# Main.net
KiCad netlist of a schematic drawn in Altium Designer
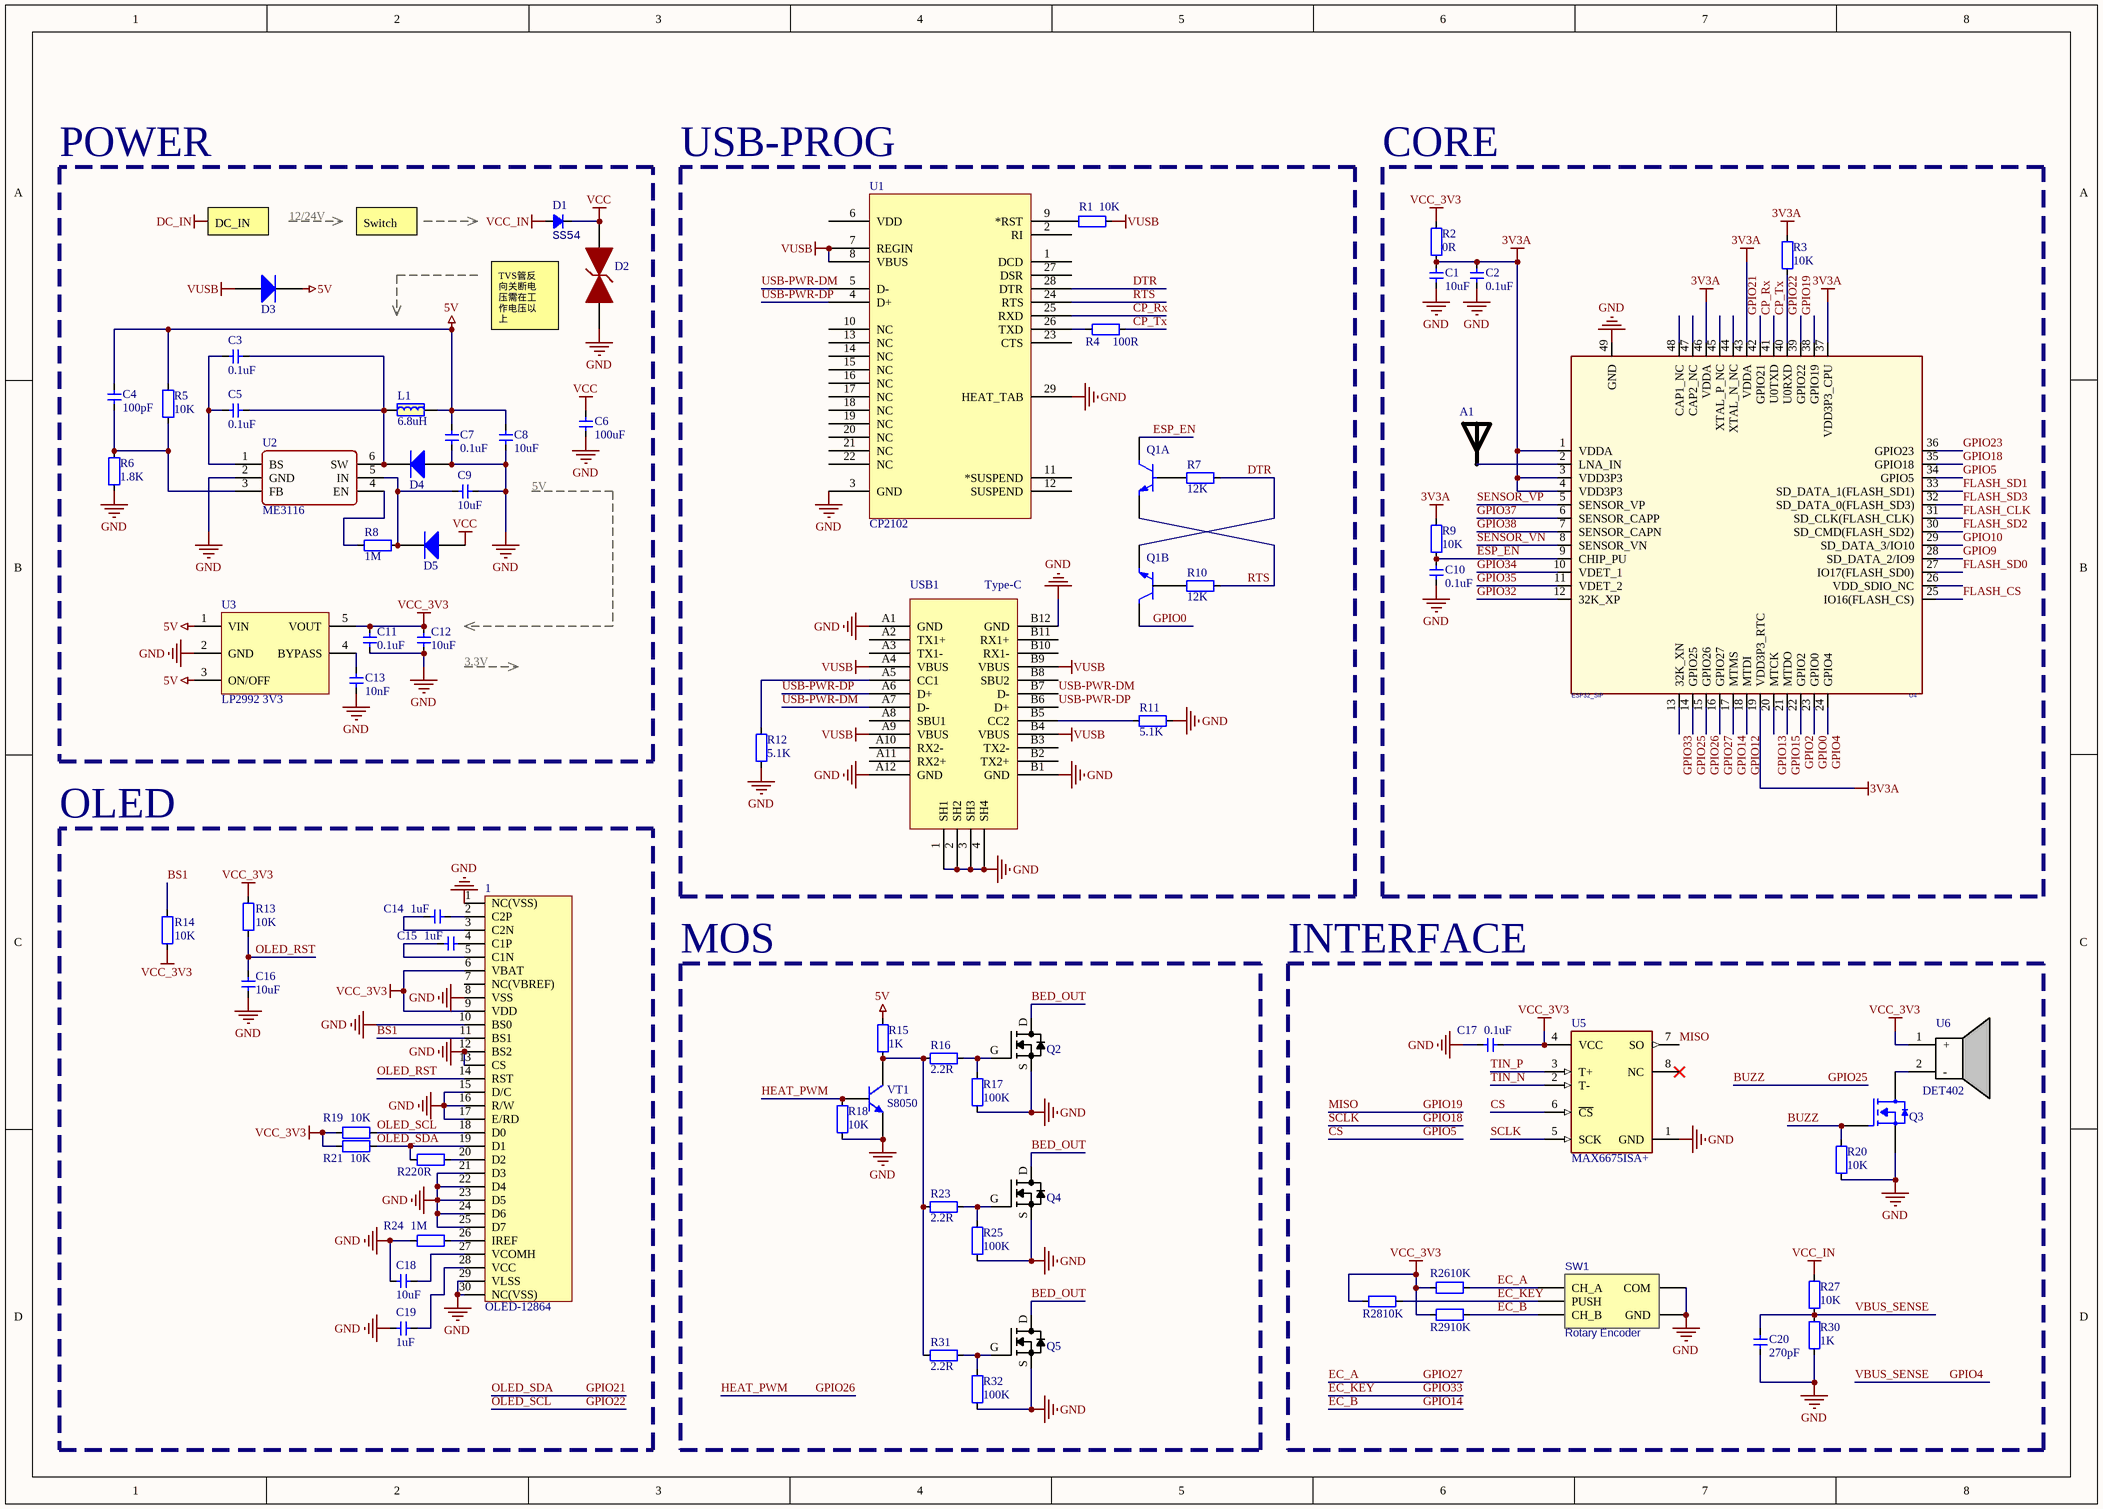
[diagram p0: Main.SchDoc]

(export (version "E")
  (design (tool "Eeschema 10.0.6"))
  (components
    (comp (ref "1")
      (value "OLED-12864")
      (footprint "OLED-12864-1.3-TOP")
      (description "显示屏")
      (libsource (lib "MyPcbLib") (part "OLED-12864"))
    )
    (comp (ref "A1")
      (value "RAINSUN")
      (footprint "ANT-Rainsun-AN5120")
      (libsource (lib "MyPcbLib") (part "ANT-Rainsun-AP5120"))
    )
    (comp (ref "C1")
      (value "10uF")
      (footprint "CAP_0402")
      (description "Capacitor")
      (libsource (lib "MyPcbLib") (part "电容-0402"))
    )
    (comp (ref "C2")
      (value "0.1uF")
      (footprint "CAP_0402")
      (description "Capacitor")
      (libsource (lib "MyPcbLib") (part "电容-0402"))
    )
    (comp (ref "C3")
      (value "0.1uF")
      (footprint "CAP_0402")
      (description "Capacitor")
      (libsource (lib "MyPcbLib") (part "电容-0402"))
    )
    (comp (ref "C4")
      (value "100pF")
      (footprint "CAP_0402")
      (description "Capacitor")
      (libsource (lib "MyPcbLib") (part "电容-0402"))
    )
    (comp (ref "C5")
      (value "0.1uF")
      (footprint "CAP_0402")
      (description "Capacitor")
      (libsource (lib "MyPcbLib") (part "电容-0402"))
    )
    (comp (ref "C6")
      (value "100uF")
      (footprint "1206-CAP")
      (description "Capacitor")
      (libsource (lib "MyPcbLib") (part "电容-1206"))
    )
    (comp (ref "C7")
      (value "0.1uF")
      (footprint "CAP_0402")
      (description "Capacitor")
      (libsource (lib "MyPcbLib") (part "电容-0402"))
    )
    (comp (ref "C8")
      (value "10uF")
      (footprint "CAP_0402")
      (description "Capacitor")
      (libsource (lib "MyPcbLib") (part "电容-0402"))
    )
    (comp (ref "C9")
      (value "10uF")
      (footprint "CAP_0402")
      (description "Capacitor")
      (libsource (lib "MyPcbLib") (part "电容-0402"))
    )
    (comp (ref "C10")
      (value "0.1uF")
      (footprint "CAP_0402")
      (description "Capacitor")
      (libsource (lib "MyPcbLib") (part "电容-0402"))
    )
    (comp (ref "C11")
      (value "0.1uF")
      (footprint "CAP_0402")
      (description "Capacitor")
      (libsource (lib "MyPcbLib") (part "电容-0402"))
    )
    (comp (ref "C12")
      (value "10uF")
      (footprint "CAP_0402")
      (description "Capacitor")
      (libsource (lib "MyPcbLib") (part "电容-0402"))
    )
    (comp (ref "C13")
      (value "10nF")
      (footprint "CAP_0402")
      (description "Capacitor")
      (libsource (lib "MyPcbLib") (part "电容-0402"))
    )
    (comp (ref "C14")
      (value "1uF")
      (footprint "CAP_0402")
      (description "Capacitor")
      (libsource (lib "MyPcbLib") (part "电容-0402"))
    )
    (comp (ref "C15")
      (value "1uF")
      (footprint "CAP_0402")
      (description "Capacitor")
      (libsource (lib "MyPcbLib") (part "电容-0402"))
    )
    (comp (ref "C16")
      (value "10uF")
      (footprint "CAP_0402")
      (description "Capacitor")
      (libsource (lib "MyPcbLib") (part "电容-0402"))
    )
    (comp (ref "C17")
      (value "0.1uF")
      (footprint "CAP_0402")
      (description "Capacitor")
      (libsource (lib "MyPcbLib") (part "电容-0402"))
    )
    (comp (ref "C18")
      (value "10uF")
      (footprint "CAP_0402")
      (description "Capacitor")
      (libsource (lib "MyPcbLib") (part "电容-0402"))
    )
    (comp (ref "C19")
      (value "1uF")
      (footprint "CAP_0402")
      (description "Capacitor")
      (libsource (lib "MyPcbLib") (part "电容-0402"))
    )
    (comp (ref "C20")
      (value "270pF")
      (footprint "CAP_0402")
      (description "Capacitor")
      (libsource (lib "MyPcbLib") (part "电容-0402"))
    )
    (comp (ref "D1")
      (value "SS54")
      (footprint "DO-214AC")
      (description "Diode")
      (libsource (lib "KitSprout") (part "Diode_SMA"))
    )
    (comp (ref "D2")
      (value "SMBJ28CA")
      (footprint "SMBJ-CA_MFG")
      (libsource (lib "MyPcbLib") (part "SMBJ28CA"))
    )
    (comp (ref "D3")
      (value "二极管-5819W")
      (footprint "SOD-323")
      (description "40V")
      (libsource (lib "MyPcbLib") (part "二极管-5819W"))
    )
    (comp (ref "D4")
      (value "二极管-5819W")
      (footprint "SOD-323")
      (description "40V")
      (libsource (lib "MyPcbLib") (part "二极管-5819W"))
    )
    (comp (ref "D5")
      (value "二极管-5819W")
      (footprint "SOD-323")
      (description "40V")
      (libsource (lib "MyPcbLib") (part "二极管-5819W"))
    )
    (comp (ref "L1") (value "6.8uH") (footprint "IND-201612") (libsource (lib "MyPcbLib") (part "电感-201612")))
    (comp (ref "Q1")
      (value "BC847BVC-7")
      (footprint "SOT563-6")
      (libsource (lib "MyPcbLib") (part "BC847BVC-7"))
    )
    (comp (ref "Q2")
      (value "NTMFS5C628NLT")
      (footprint "SO8FL")
      (description "MOSFET N-CH 60V SO8FL")
      (fields
        (field (name "MANUFACTURER") "ON Semiconductor")
        (field (name "MANUFACTURER PART NUMBER") "NTMFS5C628NLT1G")
      )
      (libsource (lib "MyPcbLib") (part "NTMFS5C628NLT"))
    )
    (comp (ref "Q3")
      (value "AO3400A")
      (footprint "SOT23-3")
      (description "N-MOS")
      (libsource (lib "MyPcbLib") (part "AO3400A"))
    )
    (comp (ref "Q4")
      (value "NTMFS5C628NLT")
      (footprint "SO8FL")
      (description "MOSFET N-CH 60V SO8FL")
      (fields
        (field (name "MANUFACTURER") "ON Semiconductor")
        (field (name "MANUFACTURER PART NUMBER") "NTMFS5C628NLT1G")
      )
      (libsource (lib "MyPcbLib") (part "NTMFS5C628NLT"))
    )
    (comp (ref "Q5")
      (value "NTMFS5C628NLT")
      (footprint "SO8FL")
      (description "MOSFET N-CH 60V SO8FL")
      (fields
        (field (name "MANUFACTURER") "ON Semiconductor")
        (field (name "MANUFACTURER PART NUMBER") "NTMFS5C628NLT1G")
      )
      (libsource (lib "MyPcbLib") (part "NTMFS5C628NLT"))
    )
    (comp (ref "R1")
      (value "10K")
      (footprint "RES_0402")
      (description "Resistor")
      (libsource (lib "MyPcbLib") (part "电阻-0402"))
    )
    (comp (ref "R2")
      (value "0R")
      (footprint "RES_0402")
      (description "Resistor")
      (libsource (lib "") (part "电阻-0402_2"))
    )
    (comp (ref "R3")
      (value "10K")
      (footprint "RES_0402")
      (description "Resistor")
      (libsource (lib "") (part "电阻-0402_1"))
    )
    (comp (ref "R4")
      (value "100R")
      (footprint "RES_0402")
      (description "Resistor")
      (libsource (lib "MyPcbLib") (part "电阻-0402"))
    )
    (comp (ref "R5")
      (value "10K")
      (footprint "RES_0402")
      (description "Resistor")
      (libsource (lib "") (part "电阻-0402_1"))
    )
    (comp (ref "R6")
      (value "1.8K")
      (footprint "RES_0402")
      (description "Resistor")
      (libsource (lib "") (part "电阻-0402_1"))
    )
    (comp (ref "R7")
      (value "12K")
      (footprint "RES_0402")
      (description "Resistor")
      (libsource (lib "MyPcbLib") (part "电阻-0402"))
    )
    (comp (ref "R8")
      (value "1M")
      (footprint "RES_0402")
      (description "Resistor")
      (libsource (lib "MyPcbLib") (part "电阻-0402"))
    )
    (comp (ref "R9")
      (value "10K")
      (footprint "RES_0402")
      (description "Resistor")
      (libsource (lib "") (part "电阻-0402_2"))
    )
    (comp (ref "R10")
      (value "12K")
      (footprint "RES_0402")
      (description "Resistor")
      (libsource (lib "MyPcbLib") (part "电阻-0402"))
    )
    (comp (ref "R11")
      (value "5.1K")
      (footprint "RES_0402")
      (description "Resistor")
      (libsource (lib "MyPcbLib") (part "电阻-0402"))
    )
    (comp (ref "R12")
      (value "5.1K")
      (footprint "RES_0402")
      (description "Resistor")
      (libsource (lib "") (part "电阻-0402_2"))
    )
    (comp (ref "R13")
      (value "10K")
      (footprint "RES_0402")
      (description "Resistor")
      (libsource (lib "") (part "电阻-0402_1"))
    )
    (comp (ref "R14")
      (value "10K")
      (footprint "RES_0402")
      (description "Resistor")
      (libsource (lib "") (part "电阻-0402_1"))
    )
    (comp (ref "R15")
      (value "1K")
      (footprint "RES_0402")
      (description "Resistor")
      (libsource (lib "") (part "电阻-0402_1"))
    )
    (comp (ref "R16")
      (value "2.2R")
      (footprint "RES_0402")
      (description "Resistor")
      (libsource (lib "MyPcbLib") (part "电阻-0402"))
    )
    (comp (ref "R17")
      (value "100K")
      (footprint "RES_0402")
      (description "Resistor")
      (libsource (lib "") (part "电阻-0402_2"))
    )
    (comp (ref "R18")
      (value "10K")
      (footprint "RES_0402")
      (description "Resistor")
      (libsource (lib "") (part "电阻-0402_2"))
    )
    (comp (ref "R19")
      (value "10K")
      (footprint "RES_0402")
      (description "Resistor")
      (libsource (lib "") (part "电阻-0402_3"))
    )
    (comp (ref "R20")
      (value "10K")
      (footprint "RES_0402")
      (description "Resistor")
      (libsource (lib "") (part "电阻-0402_1"))
    )
    (comp (ref "R21")
      (value "10K")
      (footprint "RES_0402")
      (description "Resistor")
      (libsource (lib "") (part "电阻-0402_3"))
    )
    (comp (ref "R22")
      (value "0R")
      (footprint "RES_0402")
      (description "Resistor")
      (libsource (lib "MyPcbLib") (part "电阻-0402"))
    )
    (comp (ref "R23")
      (value "2.2R")
      (footprint "RES_0402")
      (description "Resistor")
      (libsource (lib "MyPcbLib") (part "电阻-0402"))
    )
    (comp (ref "R24")
      (value "1M")
      (footprint "RES_0402")
      (description "Resistor")
      (libsource (lib "") (part "电阻-0402_3"))
    )
    (comp (ref "R25")
      (value "100K")
      (footprint "RES_0402")
      (description "Resistor")
      (libsource (lib "") (part "电阻-0402_2"))
    )
    (comp (ref "R26")
      (value "10K")
      (footprint "RES_0402")
      (description "Resistor")
      (libsource (lib "MyPcbLib") (part "电阻-0402"))
    )
    (comp (ref "R27")
      (value "10K")
      (footprint "RES_0402")
      (description "Resistor")
      (libsource (lib "") (part "电阻-0402_2"))
    )
    (comp (ref "R28")
      (value "10K")
      (footprint "RES_0402")
      (description "Resistor")
      (libsource (lib "MyPcbLib") (part "电阻-0402"))
    )
    (comp (ref "R29")
      (value "10K")
      (footprint "RES_0402")
      (description "Resistor")
      (libsource (lib "MyPcbLib") (part "电阻-0402"))
    )
    (comp (ref "R30")
      (value "1K")
      (footprint "RES_0402")
      (description "Resistor")
      (libsource (lib "") (part "电阻-0402_2"))
    )
    (comp (ref "R31")
      (value "2.2R")
      (footprint "RES_0402")
      (description "Resistor")
      (libsource (lib "MyPcbLib") (part "电阻-0402"))
    )
    (comp (ref "R32")
      (value "100K")
      (footprint "RES_0402")
      (description "Resistor")
      (libsource (lib "") (part "电阻-0402_2"))
    )
    (comp (ref "SW1")
      (value "Rotary Encoder")
      (footprint "SIQ-02FVS3")
      (fields
        (field (name "BOM_SUPPLIER PART") "C1322543")
        (field (name "BOM_MANUFACTURER PART") "EC11E1534443")
        (field (name "CONTRIBUTOR") "LCSC")
      )
      (libsource (lib "MyPcbLib") (part "Rotary Encoder"))
    )
    (comp (ref "U1")
      (value "CP2102")
      (footprint "QFN-28")
      (description "USB转TTL")
      (libsource (lib "mLib") (part "CP2102"))
    )
    (comp (ref "U2")
      (value "ME3116")
      (footprint "SOT23-6")
      (description "DC-DC")
      (libsource (lib "MyPcbLib") (part "ME3116"))
    )
    (comp (ref "U3")
      (value "LP2992 3V3")
      (footprint "SOT23-5")
      (description "LDO")
      (libsource (lib "mLib") (part "LP2992"))
    )
    (comp (ref "U4")
      (value "ESP32_SIP")
      (footprint "QFN-48_7X7")
      (libsource (lib "mLib") (part "ESP32-PICO"))
    )
    (comp (ref "U5")
      (value "MAX6675ISA")
      (footprint "SO-8")
      (description "IC THERMOCOUP TO DGTL 8-SOIC")
      (fields
        (field (name "MANUFACTURER") "Maxim Electronics")
        (field (name "OCTOPART PART NUMBER") "33bcfab92ad8ec7b")
        (field (name "PART NUMBER") "MAX6675ISA+")
      )
      (libsource (lib "MyPcbLib") (part "MAX6675ISA"))
    )
    (comp (ref "U6") (value "DET402") (footprint "DET402") (libsource (lib "MyPcbLib") (part "DET402")))
    (comp (ref "USB1")
      (value "Type-C")
      (footprint "Type-C-TOP")
      (libsource (lib "MyPcbLib") (part "USB-Type-C-TOP"))
    )
    (comp (ref "VT1")
      (value "S8050")
      (footprint "SMT_TRIODE_NPN")
      (description "Surface mount NPN transistor, package SOT-23")
      (libsource (lib "MyPcbLib") (part "SMT_TRIODE_NPN"))
    )
  )
  (nets
    (net (code "1") (name "/BED_OUT") (class "Default")
      (node (ref "Q2") (pin "D") (pinfunction "D_D") (pintype "passive"))
      (node (ref "Q4") (pin "D") (pinfunction "D_D") (pintype "passive"))
      (node (ref "Q5") (pin "D") (pinfunction "D_D") (pintype "passive"))
    )
    (net (code "2") (name "/BS1") (class "Default")
      (node (ref "1") (pin "11") (pinfunction "BS1_11") (pintype "passive"))
      (node (ref "R14") (pin "2") (pinfunction "2_2") (pintype "passive"))
    )
    (net (code "3") (name "/BUZZ") (class "Default")
      (node (ref "Q3") (pin "1") (pinfunction "G_1") (pintype "passive"))
      (node (ref "R20") (pin "2") (pinfunction "2_2") (pintype "passive"))
      (node (ref "U4") (pin "14") (pinfunction "GPIO25_14") (pintype "passive"))
    )
    (net (code "4") (name "/CP_Rx") (class "Default")
      (node (ref "U1") (pin "25") (pinfunction "RXD_25") (pintype "passive"))
      (node (ref "U4") (pin "41") (pinfunction "U0TXD_41") (pintype "power_in"))
    )
    (net (code "5") (name "/CP_Tx") (class "Default")
      (node (ref "R3") (pin "1") (pinfunction "1_1") (pintype "passive"))
      (node (ref "R4") (pin "1") (pinfunction "1_1") (pintype "passive"))
      (node (ref "U4") (pin "40") (pinfunction "U0RXD_40") (pintype "power_in"))
    )
    (net (code "6") (name "/CS") (class "Default")
      (node (ref "U4") (pin "34") (pinfunction "GPIO5_34") (pintype "passive"))
      (node (ref "U5") (pin "6") (pinfunction "~{CS}_6") (pintype "input"))
    )
    (net (code "7") (name "/DTR") (class "Default")
      (node (ref "Q1") (pin "4") (pinfunction "E2_4") (pintype "passive"))
      (node (ref "R7") (pin "1") (pinfunction "1_1") (pintype "passive"))
      (node (ref "U1") (pin "28") (pinfunction "DTR_28") (pintype "passive"))
    )
    (net (code "8") (name "/EC_A") (class "Default")
      (node (ref "R26") (pin "1") (pinfunction "1_1") (pintype "passive"))
      (node (ref "SW1") (pin "1") (pinfunction "CH_A_1") (pintype "passive"))
      (node (ref "U4") (pin "16") (pinfunction "GPIO27_16") (pintype "passive"))
    )
    (net (code "9") (name "/EC_B") (class "Default")
      (node (ref "R29") (pin "1") (pinfunction "1_1") (pintype "passive"))
      (node (ref "SW1") (pin "4") (pinfunction "CH_B_4") (pintype "passive"))
      (node (ref "U4") (pin "17") (pinfunction "MTMS_17") (pintype "passive"))
    )
    (net (code "10") (name "/EC_KEY") (class "Default")
      (node (ref "R28") (pin "1") (pinfunction "1_1") (pintype "passive"))
      (node (ref "SW1") (pin "2") (pinfunction "PUSH_2") (pintype "passive"))
      (node (ref "U4") (pin "13") (pinfunction "32K_XN_13") (pintype "passive"))
    )
    (net (code "11") (name "/ESP_EN") (class "Default")
      (node (ref "C10") (pin "1") (pinfunction "1_1") (pintype "passive"))
      (node (ref "Q1") (pin "6") (pinfunction "C1_6") (pintype "passive"))
      (node (ref "R9") (pin "2") (pinfunction "2_2") (pintype "passive"))
      (node (ref "U4") (pin "9") (pinfunction "CHIP_PU_9") (pintype "passive"))
    )
    (net (code "12") (name "/FLASH_CLK") (class "Default")
      (node (ref "U4") (pin "31") (pinfunction "SD_CLK(FLASH_CLK)_31") (pintype "passive"))
    )
    (net (code "13") (name "/FLASH_CS") (class "Default")
      (node (ref "U4") (pin "25") (pinfunction "IO16(FLASH_CS)_25") (pintype "passive"))
    )
    (net (code "14") (name "/FLASH_SD0") (class "Default")
      (node (ref "U4") (pin "27") (pinfunction "IO17(FLASH_SD0)_27") (pintype "passive"))
    )
    (net (code "15") (name "/FLASH_SD1") (class "Default")
      (node (ref "U4") (pin "33") (pinfunction "SD_DATA_1(FLASH_SD1)_33") (pintype "passive"))
    )
    (net (code "16") (name "/FLASH_SD2") (class "Default")
      (node (ref "U4") (pin "30") (pinfunction "SD_CMD(FLASH_SD2)_30") (pintype "passive"))
    )
    (net (code "17") (name "/FLASH_SD3") (class "Default")
      (node (ref "U4") (pin "32") (pinfunction "SD_DATA_0(FLASH_SD3)_32") (pintype "passive"))
    )
    (net (code "18") (name "/GPIO0") (class "Default")
      (node (ref "Q1") (pin "3") (pinfunction "C2_3") (pintype "passive"))
      (node (ref "U4") (pin "23") (pinfunction "GPIO0_23") (pintype "passive"))
    )
    (net (code "19") (name "/GPIO2") (class "Default")
      (node (ref "U4") (pin "22") (pinfunction "GPIO2_22") (pintype "passive"))
    )
    (net (code "20") (name "/GPIO4") (class "Default")
      (node (ref "C20") (pin "2") (pinfunction "2_2") (pintype "passive"))
      (node (ref "R27") (pin "2") (pinfunction "2_2") (pintype "passive"))
      (node (ref "R30") (pin "1") (pinfunction "1_1") (pintype "passive"))
      (node (ref "U4") (pin "24") (pinfunction "GPIO4_24") (pintype "passive"))
    )
    (net (code "21") (name "/GPIO9") (class "Default")
      (node (ref "U4") (pin "28") (pinfunction "SD_DATA_2/IO9_28") (pintype "passive"))
    )
    (net (code "22") (name "/GPIO10") (class "Default")
      (node (ref "U4") (pin "29") (pinfunction "SD_DATA_3/IO10_29") (pintype "passive"))
    )
    (net (code "23") (name "/GPIO12") (class "Default")
      (node (ref "U4") (pin "18") (pinfunction "MTDI_18") (pintype "passive"))
    )
    (net (code "24") (name "/GPIO13") (class "Default")
      (node (ref "U4") (pin "20") (pinfunction "MTCK_20") (pintype "passive"))
    )
    (net (code "25") (name "/GPIO15") (class "Default")
      (node (ref "U4") (pin "21") (pinfunction "MTDO_21") (pintype "passive"))
    )
    (net (code "26") (name "/GPIO18") (class "Default")
      (node (ref "U4") (pin "35") (pinfunction "GPIO18_35") (pintype "passive"))
      (node (ref "U5") (pin "5") (pinfunction "SCK_5") (pintype "input"))
    )
    (net (code "27") (name "/GPIO19") (class "Default")
      (node (ref "U4") (pin "38") (pinfunction "GPIO19_38") (pintype "passive"))
      (node (ref "U5") (pin "7") (pinfunction "SO_7") (pintype "output"))
    )
    (net (code "28") (name "/GPIO21") (class "Default")
      (node (ref "1") (pin "19") (pinfunction "D1_19") (pintype "passive"))
      (node (ref "R21") (pin "2") (pinfunction "2_2") (pintype "passive"))
      (node (ref "R22") (pin "2") (pinfunction "2_2") (pintype "passive"))
      (node (ref "U4") (pin "42") (pinfunction "GPIO21_42") (pintype "passive"))
    )
    (net (code "29") (name "/GPIO22") (class "Default")
      (node (ref "1") (pin "18") (pinfunction "D0_18") (pintype "passive"))
      (node (ref "R19") (pin "2") (pinfunction "2_2") (pintype "passive"))
      (node (ref "U4") (pin "39") (pinfunction "GPIO22_39") (pintype "passive"))
    )
    (net (code "30") (name "/GPIO23") (class "Default")
      (node (ref "U4") (pin "36") (pinfunction "GPIO23_36") (pintype "passive"))
    )
    (net (code "31") (name "/GPIO26") (class "Default")
      (node (ref "R18") (pin "1") (pinfunction "1_1") (pintype "passive"))
      (node (ref "U4") (pin "15") (pinfunction "GPIO26_15") (pintype "passive"))
      (node (ref "VT1") (pin "1") (pinfunction "B_1") (pintype "passive"))
    )
    (net (code "32") (name "/GPIO32") (class "Default")
      (node (ref "U4") (pin "12") (pinfunction "32K_XP_12") (pintype "passive"))
    )
    (net (code "33") (name "/GPIO34") (class "Default")
      (node (ref "U4") (pin "10") (pinfunction "VDET_1_10") (pintype "passive"))
    )
    (net (code "34") (name "/GPIO35") (class "Default")
      (node (ref "U4") (pin "11") (pinfunction "VDET_2_11") (pintype "passive"))
    )
    (net (code "35") (name "/GPIO37") (class "Default")
      (node (ref "U4") (pin "6") (pinfunction "SENSOR_CAPP_6") (pintype "passive"))
    )
    (net (code "36") (name "/GPIO38") (class "Default")
      (node (ref "U4") (pin "7") (pinfunction "SENSOR_CAPN_7") (pintype "passive"))
    )
    (net (code "37") (name "/OLED_RST") (class "Default")
      (node (ref "1") (pin "14") (pinfunction "RST_14") (pintype "passive"))
      (node (ref "C16") (pin "2") (pinfunction "2_2") (pintype "passive"))
      (node (ref "R13") (pin "1") (pinfunction "1_1") (pintype "passive"))
    )
    (net (code "38") (name "/RTS") (class "Default")
      (node (ref "Q1") (pin "1") (pinfunction "E1_1") (pintype "passive"))
      (node (ref "R10") (pin "1") (pinfunction "1_1") (pintype "passive"))
      (node (ref "U1") (pin "24") (pinfunction "RTS_24") (pintype "passive"))
    )
    (net (code "39") (name "/SENSOR_VN") (class "Default")
      (node (ref "U4") (pin "8") (pinfunction "SENSOR_VN_8") (pintype "passive"))
    )
    (net (code "40") (name "/SENSOR_VP") (class "Default")
      (node (ref "U4") (pin "5") (pinfunction "SENSOR_VP_5") (pintype "passive"))
    )
    (net (code "41") (name "/TIN_N") (class "Default")
      (node (ref "U5") (pin "2") (pinfunction "T-_2") (pintype "input"))
    )
    (net (code "42") (name "/TIN_P") (class "Default")
      (node (ref "U5") (pin "3") (pinfunction "T+_3") (pintype "input"))
    )
    (net (code "43") (name "/USB-PWR-DM") (class "Default")
      (node (ref "U1") (pin "5") (pinfunction "D-_5") (pintype "passive"))
      (node (ref "USB1") (pin "A7") (pinfunction "D-_A7") (pintype "passive"))
      (node (ref "USB1") (pin "B7") (pinfunction "D-_B7") (pintype "passive"))
    )
    (net (code "44") (name "/USB-PWR-DP") (class "Default")
      (node (ref "U1") (pin "4") (pinfunction "D+_4") (pintype "passive"))
      (node (ref "USB1") (pin "A6") (pinfunction "D+_A6") (pintype "passive"))
      (node (ref "USB1") (pin "B6") (pinfunction "D+_B6") (pintype "passive"))
    )
    (net (code "45") (name "3V3A") (class "Default")
      (node (ref "C1") (pin "2") (pinfunction "2_2") (pintype "passive"))
      (node (ref "C2") (pin "2") (pinfunction "2_2") (pintype "passive"))
      (node (ref "R2") (pin "2") (pinfunction "2_2") (pintype "passive"))
      (node (ref "R3") (pin "2") (pinfunction "2_2") (pintype "passive"))
      (node (ref "R9") (pin "1") (pinfunction "1_1") (pintype "passive"))
      (node (ref "U4") (pin "1") (pinfunction "VDDA_1") (pintype "power_in"))
      (node (ref "U4") (pin "19") (pinfunction "VDD3P3_RTC_19") (pintype "power_in"))
      (node (ref "U4") (pin "3") (pinfunction "VDD3P3_3") (pintype "power_in"))
      (node (ref "U4") (pin "37") (pinfunction "VDD3P3_CPU_37") (pintype "power_in"))
      (node (ref "U4") (pin "4") (pinfunction "VDD3P3_4") (pintype "power_in"))
      (node (ref "U4") (pin "43") (pinfunction "VDDA_43") (pintype "power_in"))
      (node (ref "U4") (pin "46") (pinfunction "VDDA_46") (pintype "power_in"))
    )
    (net (code "46") (name "5V") (class "Default")
      (node (ref "C4") (pin "1") (pinfunction "1_1") (pintype "passive"))
      (node (ref "C7") (pin "2") (pinfunction "2_2") (pintype "passive"))
      (node (ref "C8") (pin "2") (pinfunction "2_2") (pintype "passive"))
      (node (ref "D3") (pin "2") (pinfunction "K_2") (pintype "passive"))
      (node (ref "L1") (pin "2") (pinfunction "2_2") (pintype "passive"))
      (node (ref "R15") (pin "2") (pinfunction "2_2") (pintype "passive"))
      (node (ref "R5") (pin "2") (pinfunction "2_2") (pintype "passive"))
      (node (ref "U3") (pin "1") (pinfunction "VIN_1") (pintype "passive"))
      (node (ref "U3") (pin "3") (pinfunction "ON/OFF_3") (pintype "passive"))
    )
    (net (code "48") (name "GND") (class "Default")
      (node (ref "1") (pin "1") (pinfunction "NC(VSS)_1") (pintype "passive"))
      (node (ref "1") (pin "10") (pinfunction "BS0_10") (pintype "passive"))
      (node (ref "1") (pin "12") (pinfunction "BS2_12") (pintype "passive"))
      (node (ref "1") (pin "13") (pinfunction "CS_13") (pintype "passive"))
      (node (ref "1") (pin "15") (pinfunction "D/C_15") (pintype "passive"))
      (node (ref "1") (pin "16") (pinfunction "R/W_16") (pintype "passive"))
      (node (ref "1") (pin "17") (pinfunction "E/RD_17") (pintype "passive"))
      (node (ref "1") (pin "21") (pinfunction "D3_21") (pintype "passive"))
      (node (ref "1") (pin "22") (pinfunction "D4_22") (pintype "passive"))
      (node (ref "1") (pin "23") (pinfunction "D5_23") (pintype "passive"))
      (node (ref "1") (pin "24") (pinfunction "D6_24") (pintype "passive"))
      (node (ref "1") (pin "25") (pinfunction "D7_25") (pintype "passive"))
      (node (ref "1") (pin "29") (pinfunction "VLSS_29") (pintype "passive"))
      (node (ref "1") (pin "30") (pinfunction "NC(VSS)_30") (pintype "passive"))
      (node (ref "1") (pin "8") (pinfunction "VSS_8") (pintype "passive"))
      (node (ref "C1") (pin "1") (pinfunction "1_1") (pintype "passive"))
      (node (ref "C10") (pin "2") (pinfunction "2_2") (pintype "passive"))
      (node (ref "C11") (pin "1") (pinfunction "1_1") (pintype "passive"))
      (node (ref "C12") (pin "1") (pinfunction "1_1") (pintype "passive"))
      (node (ref "C13") (pin "1") (pinfunction "1_1") (pintype "passive"))
      (node (ref "C16") (pin "1") (pinfunction "1_1") (pintype "passive"))
      (node (ref "C17") (pin "2") (pinfunction "2_2") (pintype "passive"))
      (node (ref "C18") (pin "2") (pinfunction "2_2") (pintype "passive"))
      (node (ref "C19") (pin "2") (pinfunction "2_2") (pintype "passive"))
      (node (ref "C2") (pin "1") (pinfunction "1_1") (pintype "passive"))
      (node (ref "C20") (pin "1") (pinfunction "1_1") (pintype "passive"))
      (node (ref "C6") (pin "1") (pinfunction "1_1") (pintype "passive"))
      (node (ref "C7") (pin "1") (pinfunction "1_1") (pintype "passive"))
      (node (ref "C8") (pin "1") (pinfunction "1_1") (pintype "passive"))
      (node (ref "C9") (pin "1") (pinfunction "1_1") (pintype "passive"))
      (node (ref "D2") (pin "1") (pinfunction "1_1") (pintype "passive"))
      (node (ref "D4") (pin "1") (pinfunction "A_1") (pintype "passive"))
      (node (ref "Q2") (pin "S") (pinfunction "S_S") (pintype "passive"))
      (node (ref "Q3") (pin "2") (pinfunction "S_2") (pintype "passive"))
      (node (ref "Q4") (pin "S") (pinfunction "S_S") (pintype "passive"))
      (node (ref "Q5") (pin "S") (pinfunction "S_S") (pintype "passive"))
      (node (ref "R11") (pin "1") (pinfunction "1_1") (pintype "passive"))
      (node (ref "R12") (pin "2") (pinfunction "2_2") (pintype "passive"))
      (node (ref "R17") (pin "2") (pinfunction "2_2") (pintype "passive"))
      (node (ref "R18") (pin "2") (pinfunction "2_2") (pintype "passive"))
      (node (ref "R20") (pin "1") (pinfunction "1_1") (pintype "passive"))
      (node (ref "R24") (pin "1") (pinfunction "1_1") (pintype "passive"))
      (node (ref "R25") (pin "2") (pinfunction "2_2") (pintype "passive"))
      (node (ref "R30") (pin "2") (pinfunction "2_2") (pintype "passive"))
      (node (ref "R32") (pin "2") (pinfunction "2_2") (pintype "passive"))
      (node (ref "R6") (pin "1") (pinfunction "1_1") (pintype "passive"))
      (node (ref "SW1") (pin "3") (pinfunction "COM_3") (pintype "passive"))
      (node (ref "SW1") (pin "5") (pinfunction "GND_5") (pintype "passive"))
      (node (ref "U1") (pin "29") (pinfunction "HEAT_TAB_29") (pintype "passive"))
      (node (ref "U1") (pin "3") (pinfunction "GND_3") (pintype "passive"))
      (node (ref "U2") (pin "2") (pinfunction "GND_2") (pintype "passive"))
      (node (ref "U3") (pin "2") (pinfunction "GND_2") (pintype "passive"))
      (node (ref "U4") (pin "49") (pinfunction "GND_49") (pintype "power_in"))
      (node (ref "U5") (pin "1") (pinfunction "GND_1") (pintype "power_in"))
      (node (ref "USB1") (pin "1") (pinfunction "SH1_1") (pintype "passive"))
      (node (ref "USB1") (pin "2") (pinfunction "SH2_2") (pintype "passive"))
      (node (ref "USB1") (pin "3") (pinfunction "SH3_3") (pintype "passive"))
      (node (ref "USB1") (pin "4") (pinfunction "SH4_4") (pintype "passive"))
      (node (ref "USB1") (pin "A1") (pinfunction "GND_A1") (pintype "passive"))
      (node (ref "USB1") (pin "A12") (pinfunction "GND_A12") (pintype "passive"))
      (node (ref "USB1") (pin "B1") (pinfunction "GND_B1") (pintype "passive"))
      (node (ref "USB1") (pin "B12") (pinfunction "GND_B12") (pintype "passive"))
      (node (ref "VT1") (pin "2") (pinfunction "E_2") (pintype "passive"))
    )
    (net (code "49") (name "Net-(1-C1N)") (class "Default")
      (node (ref "1") (pin "5") (pinfunction "C1N_5") (pintype "passive"))
      (node (ref "C15") (pin "2") (pinfunction "2_2") (pintype "passive"))
    )
    (net (code "50") (name "Net-(1-C1P)") (class "Default")
      (node (ref "1") (pin "4") (pinfunction "C1P_4") (pintype "passive"))
      (node (ref "C15") (pin "1") (pinfunction "1_1") (pintype "passive"))
    )
    (net (code "51") (name "Net-(1-C2N)") (class "Default")
      (node (ref "1") (pin "3") (pinfunction "C2N_3") (pintype "passive"))
      (node (ref "C14") (pin "2") (pinfunction "2_2") (pintype "passive"))
    )
    (net (code "52") (name "Net-(1-C2P)") (class "Default")
      (node (ref "1") (pin "2") (pinfunction "C2P_2") (pintype "passive"))
      (node (ref "C14") (pin "1") (pinfunction "1_1") (pintype "passive"))
    )
    (net (code "53") (name "Net-(1-D2)") (class "Default")
      (node (ref "1") (pin "20") (pinfunction "D2_20") (pintype "passive"))
      (node (ref "R22") (pin "1") (pinfunction "1_1") (pintype "passive"))
    )
    (net (code "54") (name "Net-(1-IREF)") (class "Default")
      (node (ref "1") (pin "26") (pinfunction "IREF_26") (pintype "passive"))
      (node (ref "R24") (pin "2") (pinfunction "2_2") (pintype "passive"))
    )
    (net (code "55") (name "Net-(1-VCC)") (class "Default")
      (node (ref "1") (pin "28") (pinfunction "VCC_28") (pintype "passive"))
      (node (ref "C19") (pin "1") (pinfunction "1_1") (pintype "passive"))
    )
    (net (code "56") (name "Net-(1-VCOMH)") (class "Default")
      (node (ref "1") (pin "27") (pinfunction "VCOMH_27") (pintype "passive"))
      (node (ref "C18") (pin "1") (pinfunction "1_1") (pintype "passive"))
    )
    (net (code "57") (name "Net-(D4-K)") (class "Default")
      (node (ref "C3") (pin "1") (pinfunction "1_1") (pintype "passive"))
      (node (ref "C5") (pin "1") (pinfunction "1_1") (pintype "passive"))
      (node (ref "D4") (pin "2") (pinfunction "K_2") (pintype "passive"))
      (node (ref "L1") (pin "1") (pintype "passive"))
      (node (ref "U2") (pin "6") (pinfunction "SW_6") (pintype "passive"))
    )
    (net (code "58") (name "Net-(D5-K)") (class "Default")
      (node (ref "C9") (pin "2") (pinfunction "2_2") (pintype "passive"))
      (node (ref "D5") (pin "2") (pinfunction "K_2") (pintype "passive"))
      (node (ref "R8") (pin "1") (pinfunction "1_1") (pintype "passive"))
      (node (ref "U2") (pin "5") (pinfunction "IN_5") (pintype "passive"))
    )
    (net (code "59") (name "Net-(Q1A-B1)") (class "Default")
      (node (ref "Q1") (pin "2") (pinfunction "B1_2") (pintype "passive"))
      (node (ref "R7") (pin "2") (pinfunction "2_2") (pintype "passive"))
    )
    (net (code "60") (name "Net-(Q1B-B2)") (class "Default")
      (node (ref "Q1") (pin "5") (pinfunction "B2_5") (pintype "passive"))
      (node (ref "R10") (pin "2") (pinfunction "2_2") (pintype "passive"))
    )
    (net (code "61") (name "Net-(Q2-PadG)") (class "Default")
      (node (ref "Q2") (pin "G") (pinfunction "G_G") (pintype "passive"))
      (node (ref "R16") (pin "1") (pinfunction "1_1") (pintype "passive"))
      (node (ref "R17") (pin "1") (pinfunction "1_1") (pintype "passive"))
    )
    (net (code "62") (name "Net-(Q3-D)") (class "Default")
      (node (ref "Q3") (pin "3") (pinfunction "D_3") (pintype "passive"))
      (node (ref "U6") (pin "2") (pinfunction "-_2") (pintype "passive"))
    )
    (net (code "63") (name "Net-(Q4-PadG)") (class "Default")
      (node (ref "Q4") (pin "G") (pinfunction "G_G") (pintype "passive"))
      (node (ref "R23") (pin "1") (pinfunction "1_1") (pintype "passive"))
      (node (ref "R25") (pin "1") (pinfunction "1_1") (pintype "passive"))
    )
    (net (code "64") (name "Net-(Q5-PadG)") (class "Default")
      (node (ref "Q5") (pin "G") (pinfunction "G_G") (pintype "passive"))
      (node (ref "R31") (pin "1") (pinfunction "1_1") (pintype "passive"))
      (node (ref "R32") (pin "1") (pinfunction "1_1") (pintype "passive"))
    )
    (net (code "65") (name "Net-(U1-*RST)") (class "Default")
      (node (ref "R1") (pin "2") (pinfunction "2_2") (pintype "passive"))
      (node (ref "U1") (pin "9") (pinfunction "*RST_9") (pintype "passive"))
    )
    (net (code "66") (name "Net-(U1-TXD)") (class "Default")
      (node (ref "R4") (pin "2") (pinfunction "2_2") (pintype "passive"))
      (node (ref "U1") (pin "26") (pinfunction "TXD_26") (pintype "passive"))
    )
    (net (code "67") (name "Net-(U2-BS)") (class "Default")
      (node (ref "C3") (pin "2") (pinfunction "2_2") (pintype "passive"))
      (node (ref "C5") (pin "2") (pinfunction "2_2") (pintype "passive"))
      (node (ref "U2") (pin "1") (pinfunction "BS_1") (pintype "passive"))
    )
    (net (code "68") (name "Net-(U2-EN)") (class "Default")
      (node (ref "R8") (pin "2") (pinfunction "2_2") (pintype "passive"))
      (node (ref "U2") (pin "4") (pinfunction "EN_4") (pintype "passive"))
    )
    (net (code "69") (name "Net-(U2-FB)") (class "Default")
      (node (ref "C4") (pin "2") (pinfunction "2_2") (pintype "passive"))
      (node (ref "R5") (pin "1") (pinfunction "1_1") (pintype "passive"))
      (node (ref "R6") (pin "2") (pinfunction "2_2") (pintype "passive"))
      (node (ref "U2") (pin "3") (pinfunction "FB_3") (pintype "passive"))
    )
    (net (code "70") (name "Net-(U3-BYPASS)") (class "Default")
      (node (ref "C13") (pin "2") (pinfunction "2_2") (pintype "passive"))
      (node (ref "U3") (pin "4") (pinfunction "BYPASS_4") (pintype "passive"))
    )
    (net (code "71") (name "Net-(U4-LNA_IN)") (class "Default")
      (node (ref "A1") (pin "1") (pinfunction "1_1") (pintype "passive"))
      (node (ref "U4") (pin "2") (pinfunction "LNA_IN_2") (pintype "passive"))
    )
    (net (code "72") (name "Net-(USB1-CC1)") (class "Default")
      (node (ref "R12") (pin "1") (pinfunction "1_1") (pintype "passive"))
      (node (ref "USB1") (pin "A5") (pinfunction "CC1_A5") (pintype "passive"))
    )
    (net (code "73") (name "Net-(USB1-CC2)") (class "Default")
      (node (ref "R11") (pin "2") (pinfunction "2_2") (pintype "passive"))
      (node (ref "USB1") (pin "B5") (pinfunction "CC2_B5") (pintype "passive"))
    )
    (net (code "74") (name "Net-(VT1-C)") (class "Default")
      (node (ref "R15") (pin "1") (pinfunction "1_1") (pintype "passive"))
      (node (ref "R16") (pin "2") (pinfunction "2_2") (pintype "passive"))
      (node (ref "R23") (pin "2") (pinfunction "2_2") (pintype "passive"))
      (node (ref "R31") (pin "2") (pinfunction "2_2") (pintype "passive"))
      (node (ref "VT1") (pin "3") (pinfunction "C_3") (pintype "passive"))
    )
    (net (code "75") (name "VCC") (class "Default")
      (node (ref "C6") (pin "2") (pinfunction "2_2") (pintype "passive"))
      (node (ref "D1") (pin "2") (pinfunction "K_2") (pintype "passive"))
      (node (ref "D2") (pin "2") (pinfunction "2_2") (pintype "passive"))
      (node (ref "D5") (pin "1") (pinfunction "A_1") (pintype "passive"))
    )
    (net (code "76") (name "VCC_3V3") (class "Default")
      (node (ref "1") (pin "6") (pinfunction "VBAT_6") (pintype "passive"))
      (node (ref "1") (pin "9") (pinfunction "VDD_9") (pintype "passive"))
      (node (ref "C11") (pin "2") (pinfunction "2_2") (pintype "passive"))
      (node (ref "C12") (pin "2") (pinfunction "2_2") (pintype "passive"))
      (node (ref "C17") (pin "1") (pinfunction "1_1") (pintype "passive"))
      (node (ref "R13") (pin "2") (pinfunction "2_2") (pintype "passive"))
      (node (ref "R14") (pin "1") (pinfunction "1_1") (pintype "passive"))
      (node (ref "R19") (pin "1") (pinfunction "1_1") (pintype "passive"))
      (node (ref "R2") (pin "1") (pinfunction "1_1") (pintype "passive"))
      (node (ref "R21") (pin "1") (pinfunction "1_1") (pintype "passive"))
      (node (ref "R26") (pin "2") (pinfunction "2_2") (pintype "passive"))
      (node (ref "R28") (pin "2") (pinfunction "2_2") (pintype "passive"))
      (node (ref "R29") (pin "2") (pinfunction "2_2") (pintype "passive"))
      (node (ref "U3") (pin "5") (pinfunction "VOUT_5") (pintype "passive"))
      (node (ref "U5") (pin "4") (pinfunction "VCC_4") (pintype "power_in"))
      (node (ref "U6") (pin "1") (pinfunction "+_1") (pintype "passive"))
    )
    (net (code "77") (name "VCC_IN") (class "Default")
      (node (ref "D1") (pin "1") (pinfunction "A_1") (pintype "passive"))
      (node (ref "R27") (pin "1") (pinfunction "1_1") (pintype "passive"))
    )
    (net (code "78") (name "VUSB") (class "Default")
      (node (ref "D3") (pin "1") (pinfunction "A_1") (pintype "passive"))
      (node (ref "R1") (pin "1") (pinfunction "1_1") (pintype "passive"))
      (node (ref "U1") (pin "7") (pinfunction "REGIN_7") (pintype "passive"))
      (node (ref "U1") (pin "8") (pinfunction "VBUS_8") (pintype "passive"))
      (node (ref "USB1") (pin "A4") (pinfunction "VBUS_A4") (pintype "passive"))
      (node (ref "USB1") (pin "A9") (pinfunction "VBUS_A9") (pintype "passive"))
      (node (ref "USB1") (pin "B4") (pinfunction "VBUS_B4") (pintype "passive"))
      (node (ref "USB1") (pin "B9") (pinfunction "VBUS_B9") (pintype "passive"))
    )
    (net (code "79") (name "unconnected-(1-NC(VBREF)-Pad7)") (class "Default")
      (node (ref "1") (pin "7") (pinfunction "NC(VBREF)_7") (pintype "passive"))
    )
    (net (code "80") (name "unconnected-(U1-*SUSPEND-Pad11)") (class "Default")
      (node (ref "U1") (pin "11") (pinfunction "*SUSPEND_11") (pintype "passive"))
    )
    (net (code "81") (name "unconnected-(U1-CTS-Pad23)") (class "Default")
      (node (ref "U1") (pin "23") (pinfunction "CTS_23") (pintype "passive"))
    )
    (net (code "82") (name "unconnected-(U1-DCD-Pad1)") (class "Default")
      (node (ref "U1") (pin "1") (pinfunction "DCD_1") (pintype "passive"))
    )
    (net (code "83") (name "unconnected-(U1-DSR-Pad27)") (class "Default")
      (node (ref "U1") (pin "27") (pinfunction "DSR_27") (pintype "passive"))
    )
    (net (code "84") (name "unconnected-(U1-NC-Pad10)") (class "Default")
      (node (ref "U1") (pin "10") (pinfunction "NC_10") (pintype "passive"))
    )
    (net (code "85") (name "unconnected-(U1-NC-Pad13)") (class "Default")
      (node (ref "U1") (pin "13") (pinfunction "NC_13") (pintype "passive"))
    )
    (net (code "86") (name "unconnected-(U1-NC-Pad14)") (class "Default")
      (node (ref "U1") (pin "14") (pinfunction "NC_14") (pintype "passive"))
    )
    (net (code "87") (name "unconnected-(U1-NC-Pad15)") (class "Default")
      (node (ref "U1") (pin "15") (pinfunction "NC_15") (pintype "passive"))
    )
    (net (code "88") (name "unconnected-(U1-NC-Pad16)") (class "Default")
      (node (ref "U1") (pin "16") (pinfunction "NC_16") (pintype "passive"))
    )
    (net (code "89") (name "unconnected-(U1-NC-Pad17)") (class "Default")
      (node (ref "U1") (pin "17") (pinfunction "NC_17") (pintype "passive"))
    )
    (net (code "90") (name "unconnected-(U1-NC-Pad18)") (class "Default")
      (node (ref "U1") (pin "18") (pinfunction "NC_18") (pintype "passive"))
    )
    (net (code "91") (name "unconnected-(U1-NC-Pad19)") (class "Default")
      (node (ref "U1") (pin "19") (pinfunction "NC_19") (pintype "passive"))
    )
    (net (code "92") (name "unconnected-(U1-NC-Pad20)") (class "Default")
      (node (ref "U1") (pin "20") (pinfunction "NC_20") (pintype "passive"))
    )
    (net (code "93") (name "unconnected-(U1-NC-Pad21)") (class "Default")
      (node (ref "U1") (pin "21") (pinfunction "NC_21") (pintype "passive"))
    )
    (net (code "94") (name "unconnected-(U1-NC-Pad22)") (class "Default")
      (node (ref "U1") (pin "22") (pinfunction "NC_22") (pintype "passive"))
    )
    (net (code "95") (name "unconnected-(U1-RI-Pad2)") (class "Default")
      (node (ref "U1") (pin "2") (pinfunction "RI_2") (pintype "passive"))
    )
    (net (code "96") (name "unconnected-(U1-SUSPEND-Pad12)") (class "Default")
      (node (ref "U1") (pin "12") (pinfunction "SUSPEND_12") (pintype "passive"))
    )
    (net (code "97") (name "unconnected-(U1-VDD-Pad6)") (class "Default")
      (node (ref "U1") (pin "6") (pinfunction "VDD_6") (pintype "passive"))
    )
    (net (code "98") (name "unconnected-(U4-CAP1_NC-Pad48)") (class "Default")
      (node (ref "U4") (pin "48") (pinfunction "CAP1_NC_48") (pintype "passive"))
    )
    (net (code "99") (name "unconnected-(U4-CAP2_NC-Pad47)") (class "Default")
      (node (ref "U4") (pin "47") (pinfunction "CAP2_NC_47") (pintype "passive"))
    )
    (net (code "100") (name "unconnected-(U4-VDD_SDIO_NC-Pad26)") (class "Default")
      (node (ref "U4") (pin "26") (pinfunction "VDD_SDIO_NC_26") (pintype "passive"))
    )
    (net (code "101") (name "unconnected-(U4-XTAL_N_NC-Pad44)") (class "Default")
      (node (ref "U4") (pin "44") (pinfunction "XTAL_N_NC_44") (pintype "passive"))
    )
    (net (code "102") (name "unconnected-(U4-XTAL_P_NC-Pad45)") (class "Default")
      (node (ref "U4") (pin "45") (pinfunction "XTAL_P_NC_45") (pintype "passive"))
    )
    (net (code "103") (name "unconnected-(U5-NC-Pad8)") (class "Default")
      (node (ref "U5") (pin "8") (pinfunction "NC_8") (pintype "passive+no_connect"))
    )
    (net (code "104") (name "unconnected-(USB1-RX1+-PadB11)") (class "Default")
      (node (ref "USB1") (pin "B11") (pinfunction "RX1+_B11") (pintype "passive"))
    )
    (net (code "105") (name "unconnected-(USB1-RX1--PadB10)") (class "Default")
      (node (ref "USB1") (pin "B10") (pinfunction "RX1-_B10") (pintype "passive"))
    )
    (net (code "106") (name "unconnected-(USB1-RX2+-PadA11)") (class "Default")
      (node (ref "USB1") (pin "A11") (pinfunction "RX2+_A11") (pintype "passive"))
    )
    (net (code "107") (name "unconnected-(USB1-RX2--PadA10)") (class "Default")
      (node (ref "USB1") (pin "A10") (pinfunction "RX2-_A10") (pintype "passive"))
    )
    (net (code "108") (name "unconnected-(USB1-SBU1-PadA8)") (class "Default")
      (node (ref "USB1") (pin "A8") (pinfunction "SBU1_A8") (pintype "passive"))
    )
    (net (code "109") (name "unconnected-(USB1-SBU2-PadB8)") (class "Default")
      (node (ref "USB1") (pin "B8") (pinfunction "SBU2_B8") (pintype "passive"))
    )
    (net (code "110") (name "unconnected-(USB1-TX1+-PadA2)") (class "Default")
      (node (ref "USB1") (pin "A2") (pinfunction "TX1+_A2") (pintype "passive"))
    )
    (net (code "111") (name "unconnected-(USB1-TX1--PadA3)") (class "Default")
      (node (ref "USB1") (pin "A3") (pinfunction "TX1-_A3") (pintype "passive"))
    )
    (net (code "112") (name "unconnected-(USB1-TX2+-PadB2)") (class "Default")
      (node (ref "USB1") (pin "B2") (pinfunction "TX2+_B2") (pintype "passive"))
    )
    (net (code "113") (name "unconnected-(USB1-TX2--PadB3)") (class "Default")
      (node (ref "USB1") (pin "B3") (pinfunction "TX2-_B3") (pintype "passive"))
    )
  )
)
